# mowbot.net
KiCad netlist of a schematic drawn in EAGLE
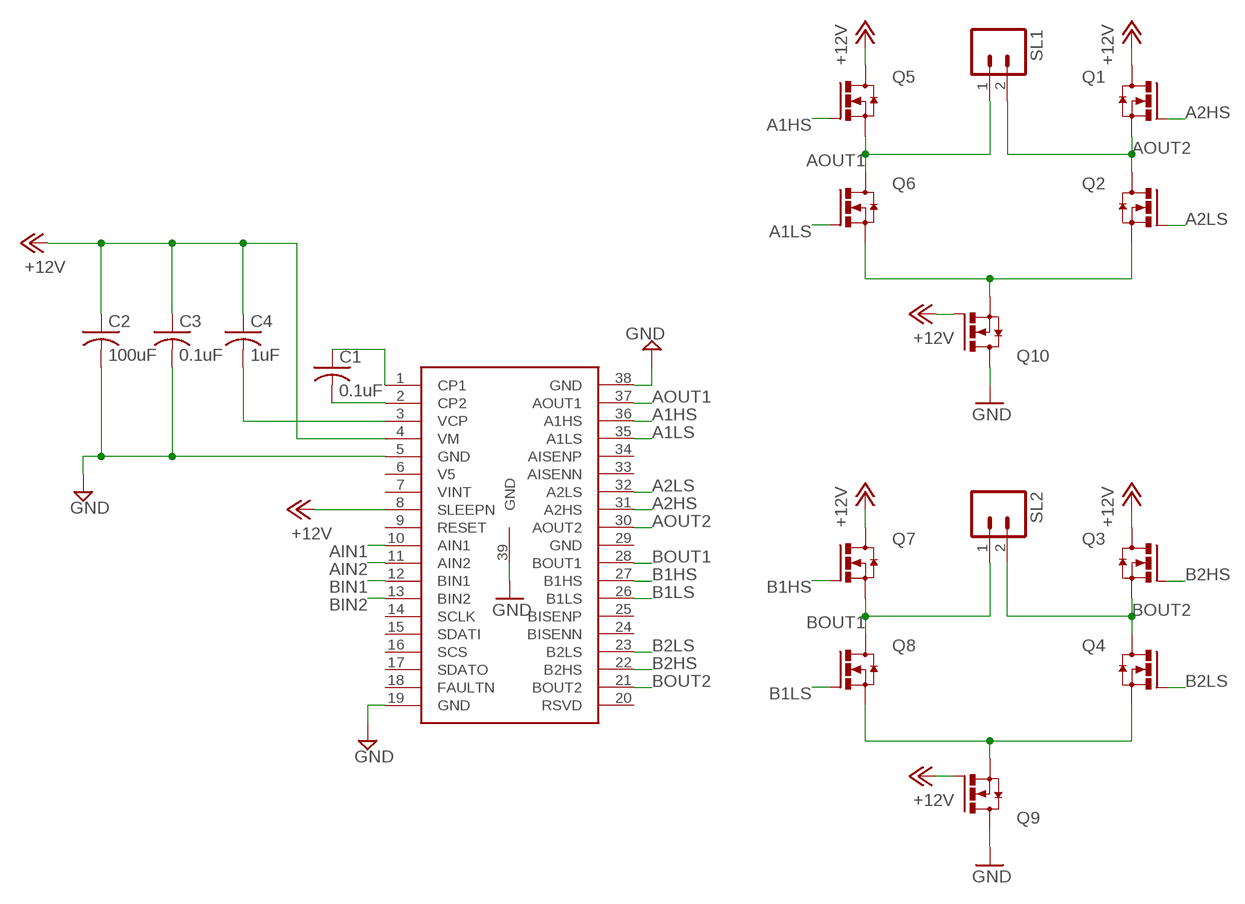
[diagram p0: schematic, sheet 1]
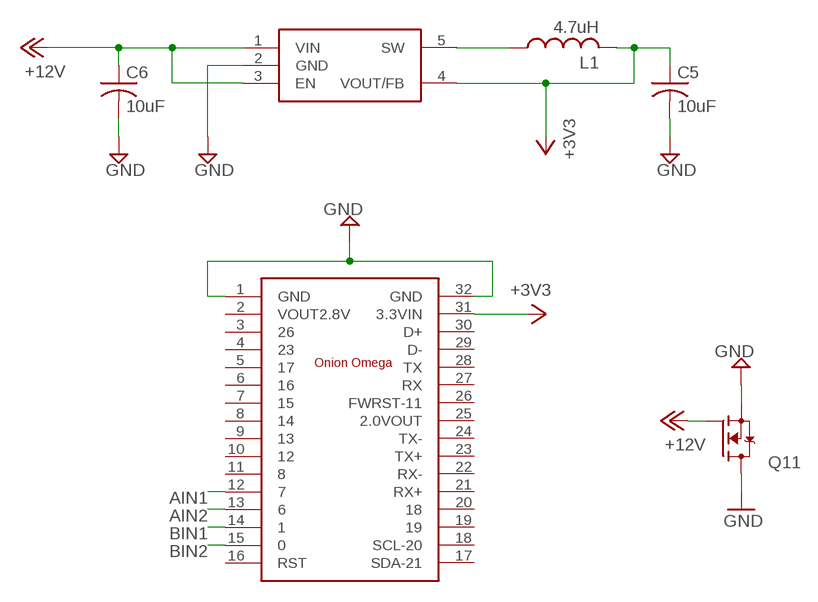
[diagram p1: schematic, sheet 2]

(export (version "E")
  (design (tool "Eeschema 10.0.6"))
  (components
    (comp (ref "C1")
      (value "0.1uF")
      (footprint "eagle-import:C0603")
      (libsource (lib "eagle-import") (part "C-USC0603"))
    )
    (comp (ref "C2")
      (value "100uF")
      (footprint "eagle-import:C0603")
      (libsource (lib "eagle-import") (part "C-USC0603"))
    )
    (comp (ref "C3")
      (value "0.1uF")
      (footprint "eagle-import:C0603")
      (libsource (lib "eagle-import") (part "C-USC0603"))
    )
    (comp (ref "C4")
      (value "1uF")
      (footprint "eagle-import:C0603")
      (libsource (lib "eagle-import") (part "C-USC0603"))
    )
    (comp (ref "Q1")
      (value "PSMN9R1-30YL-MOSFET_N")
      (footprint "eagle-import:SOT669")
      (libsource (lib "eagle-import") (part "PSMN9R1-30YL-MOSFET_N"))
    )
    (comp (ref "Q2")
      (value "PSMN9R1-30YL-MOSFET_N")
      (footprint "eagle-import:SOT669")
      (libsource (lib "eagle-import") (part "PSMN9R1-30YL-MOSFET_N"))
    )
    (comp (ref "Q3")
      (value "PSMN9R1-30YL-MOSFET_N")
      (footprint "eagle-import:SOT669")
      (libsource (lib "eagle-import") (part "PSMN9R1-30YL-MOSFET_N"))
    )
    (comp (ref "Q4")
      (value "PSMN9R1-30YL-MOSFET_N")
      (footprint "eagle-import:SOT669")
      (libsource (lib "eagle-import") (part "PSMN9R1-30YL-MOSFET_N"))
    )
    (comp (ref "Q5")
      (value "PSMN9R1-30YL-MOSFET_N")
      (footprint "eagle-import:SOT669")
      (libsource (lib "eagle-import") (part "PSMN9R1-30YL-MOSFET_N"))
    )
    (comp (ref "Q6")
      (value "PSMN9R1-30YL-MOSFET_N")
      (footprint "eagle-import:SOT669")
      (libsource (lib "eagle-import") (part "PSMN9R1-30YL-MOSFET_N"))
    )
    (comp (ref "Q7")
      (value "PSMN9R1-30YL-MOSFET_N")
      (footprint "eagle-import:SOT669")
      (libsource (lib "eagle-import") (part "PSMN9R1-30YL-MOSFET_N"))
    )
    (comp (ref "Q8")
      (value "PSMN9R1-30YL-MOSFET_N")
      (footprint "eagle-import:SOT669")
      (libsource (lib "eagle-import") (part "PSMN9R1-30YL-MOSFET_N"))
    )
    (comp (ref "Q9")
      (value "PSMN9R1-30YL-MOSFET_N")
      (footprint "eagle-import:SOT669")
      (libsource (lib "eagle-import") (part "PSMN9R1-30YL-MOSFET_N"))
    )
    (comp (ref "Q10")
      (value "PSMN9R1-30YL-MOSFET_N")
      (footprint "eagle-import:SOT669")
      (libsource (lib "eagle-import") (part "PSMN9R1-30YL-MOSFET_N"))
    )
    (comp (ref "SL1")
      (value "M02")
      (footprint "eagle-import:02P")
      (libsource (lib "eagle-import") (part "M02"))
    )
    (comp (ref "SL2")
      (value "M02")
      (footprint "eagle-import:02P")
      (libsource (lib "eagle-import") (part "M02"))
    )
    (comp (ref "U$1")
      (value "DRV8704-HBRIDGE_DRIVER")
      (footprint "eagle-import:DRV8704-HBRIDGE-DRIVER")
      (libsource (lib "eagle-import") (part "DRV8704-HBRIDGE_DRIVER"))
    )
    (comp (ref "C5")
      (value "10uF")
      (footprint "eagle-import:C0603")
      (libsource (lib "eagle-import") (part "C-USC0603"))
    )
    (comp (ref "C6")
      (value "10uF")
      (footprint "eagle-import:C0603")
      (libsource (lib "eagle-import") (part "C-USC0603"))
    )
    (comp (ref "L1")
      (value "4.7uH")
      (footprint "eagle-import:L1812")
      (libsource (lib "eagle-import") (part "L-USL1812"))
    )
    (comp (ref "Q11")
      (value "DMG2302UK-NMOSFET")
      (footprint "eagle-import:SOT23")
      (libsource (lib "eagle-import") (part "DMG2302UK-NMOSFET"))
    )
    (comp (ref "U$2")
      (value "ONION_OMEGA")
      (footprint "eagle-import:ONION_OMEGA")
      (libsource (lib "eagle-import") (part "ONION_OMEGA"))
    )
    (comp (ref "U$3")
      (value "PAM2305")
      (footprint "eagle-import:SOT23-5")
      (libsource (lib "eagle-import") (part "PAM2305"))
    )
  )
  (nets
    (net (code "1") (name "+3V3") (class "Default")
      (node (ref "C5") (pin "1") (pinfunction "1_1") (pintype "passive"))
      (node (ref "L1") (pin "2") (pinfunction "2_2") (pintype "passive"))
      (node (ref "U$2") (pin "31") (pinfunction "3.3VIN_31") (pintype "bidirectional"))
      (node (ref "U$3") (pin "4") (pinfunction "VOUT/FB_4") (pintype "bidirectional"))
    )
    (net (code "2") (name "+12V") (class "Default")
      (node (ref "C2") (pin "1") (pinfunction "1_1") (pintype "passive"))
      (node (ref "C3") (pin "1") (pinfunction "1_1") (pintype "passive"))
      (node (ref "C4") (pin "1") (pinfunction "1_1") (pintype "passive"))
      (node (ref "C6") (pin "1") (pinfunction "1_1") (pintype "passive"))
      (node (ref "Q1") (pin "MB") (pinfunction "D_MB") (pintype "passive"))
      (node (ref "Q10") (pin "4") (pinfunction "G_4") (pintype "passive"))
      (node (ref "Q11") (pin "1") (pinfunction "G_1") (pintype "passive"))
      (node (ref "Q3") (pin "MB") (pinfunction "D_MB") (pintype "passive"))
      (node (ref "Q5") (pin "MB") (pinfunction "D_MB") (pintype "passive"))
      (node (ref "Q7") (pin "MB") (pinfunction "D_MB") (pintype "passive"))
      (node (ref "Q9") (pin "4") (pinfunction "G_4") (pintype "passive"))
      (node (ref "U$1") (pin "4") (pinfunction "VM_4") (pintype "bidirectional"))
      (node (ref "U$1") (pin "8") (pinfunction "SLEEPN_8") (pintype "bidirectional"))
      (node (ref "U$3") (pin "1") (pinfunction "VIN_1") (pintype "bidirectional"))
      (node (ref "U$3") (pin "3") (pinfunction "EN_3") (pintype "bidirectional"))
    )
    (net (code "3") (name "A1HS") (class "Default")
      (node (ref "Q5") (pin "4") (pinfunction "G_4") (pintype "passive"))
      (node (ref "U$1") (pin "36") (pinfunction "A1HS_36") (pintype "bidirectional"))
    )
    (net (code "4") (name "A1LS") (class "Default")
      (node (ref "Q6") (pin "4") (pinfunction "G_4") (pintype "passive"))
      (node (ref "U$1") (pin "35") (pinfunction "A1LS_35") (pintype "bidirectional"))
    )
    (net (code "5") (name "A2HS") (class "Default")
      (node (ref "Q1") (pin "4") (pinfunction "G_4") (pintype "passive"))
      (node (ref "U$1") (pin "31") (pinfunction "A2HS_31") (pintype "bidirectional"))
    )
    (net (code "6") (name "A2LS") (class "Default")
      (node (ref "Q2") (pin "4") (pinfunction "G_4") (pintype "passive"))
      (node (ref "U$1") (pin "32") (pinfunction "A2LS_32") (pintype "bidirectional"))
    )
    (net (code "7") (name "AIN1") (class "Default")
      (node (ref "U$1") (pin "10") (pinfunction "AIN1_10") (pintype "bidirectional"))
      (node (ref "U$2") (pin "12") (pinfunction "7_12") (pintype "bidirectional"))
    )
    (net (code "8") (name "AIN2") (class "Default")
      (node (ref "U$1") (pin "11") (pinfunction "AIN2_11") (pintype "bidirectional"))
      (node (ref "U$2") (pin "13") (pinfunction "6_13") (pintype "bidirectional"))
    )
    (net (code "9") (name "AOUT1") (class "Default")
      (node (ref "Q5") (pin "1") (pinfunction "S_1") (pintype "passive"))
      (node (ref "Q5") (pin "2") (pinfunction "S_2") (pintype "passive"))
      (node (ref "Q5") (pin "3") (pinfunction "S_3") (pintype "passive"))
      (node (ref "Q6") (pin "MB") (pinfunction "D_MB") (pintype "passive"))
      (node (ref "SL1") (pin "1") (pinfunction "1_1") (pintype "passive"))
      (node (ref "U$1") (pin "37") (pinfunction "AOUT1_37") (pintype "bidirectional"))
    )
    (net (code "10") (name "AOUT2") (class "Default")
      (node (ref "Q1") (pin "1") (pinfunction "S_1") (pintype "passive"))
      (node (ref "Q1") (pin "2") (pinfunction "S_2") (pintype "passive"))
      (node (ref "Q1") (pin "3") (pinfunction "S_3") (pintype "passive"))
      (node (ref "Q2") (pin "MB") (pinfunction "D_MB") (pintype "passive"))
      (node (ref "SL1") (pin "2") (pinfunction "2_2") (pintype "passive"))
      (node (ref "U$1") (pin "30") (pinfunction "AOUT2_30") (pintype "bidirectional"))
    )
    (net (code "11") (name "B1HS") (class "Default")
      (node (ref "Q7") (pin "4") (pinfunction "G_4") (pintype "passive"))
      (node (ref "U$1") (pin "27") (pinfunction "B1HS_27") (pintype "bidirectional"))
    )
    (net (code "12") (name "B1LS") (class "Default")
      (node (ref "Q8") (pin "4") (pinfunction "G_4") (pintype "passive"))
      (node (ref "U$1") (pin "26") (pinfunction "B1LS_26") (pintype "bidirectional"))
    )
    (net (code "13") (name "B2HS") (class "Default")
      (node (ref "Q3") (pin "4") (pinfunction "G_4") (pintype "passive"))
      (node (ref "U$1") (pin "22") (pinfunction "B2HS_22") (pintype "bidirectional"))
    )
    (net (code "14") (name "B2LS") (class "Default")
      (node (ref "Q4") (pin "4") (pinfunction "G_4") (pintype "passive"))
      (node (ref "U$1") (pin "23") (pinfunction "B2LS_23") (pintype "bidirectional"))
    )
    (net (code "15") (name "BIN1") (class "Default")
      (node (ref "U$1") (pin "12") (pinfunction "BIN1_12") (pintype "bidirectional"))
      (node (ref "U$2") (pin "14") (pinfunction "1_14") (pintype "bidirectional"))
    )
    (net (code "16") (name "BIN2") (class "Default")
      (node (ref "U$1") (pin "13") (pinfunction "BIN2_13") (pintype "bidirectional"))
      (node (ref "U$2") (pin "15") (pinfunction "0_15") (pintype "bidirectional"))
    )
    (net (code "17") (name "BOUT1") (class "Default")
      (node (ref "Q7") (pin "1") (pinfunction "S_1") (pintype "passive"))
      (node (ref "Q7") (pin "2") (pinfunction "S_2") (pintype "passive"))
      (node (ref "Q7") (pin "3") (pinfunction "S_3") (pintype "passive"))
      (node (ref "Q8") (pin "MB") (pinfunction "D_MB") (pintype "passive"))
      (node (ref "SL2") (pin "1") (pinfunction "1_1") (pintype "passive"))
      (node (ref "U$1") (pin "28") (pinfunction "BOUT1_28") (pintype "bidirectional"))
    )
    (net (code "18") (name "BOUT2") (class "Default")
      (node (ref "Q3") (pin "1") (pinfunction "S_1") (pintype "passive"))
      (node (ref "Q3") (pin "2") (pinfunction "S_2") (pintype "passive"))
      (node (ref "Q3") (pin "3") (pinfunction "S_3") (pintype "passive"))
      (node (ref "Q4") (pin "MB") (pinfunction "D_MB") (pintype "passive"))
      (node (ref "SL2") (pin "2") (pinfunction "2_2") (pintype "passive"))
      (node (ref "U$1") (pin "21") (pinfunction "BOUT2_21") (pintype "bidirectional"))
    )
    (net (code "19") (name "GND") (class "Default")
      (node (ref "C2") (pin "2") (pinfunction "2_2") (pintype "passive"))
      (node (ref "C3") (pin "2") (pinfunction "2_2") (pintype "passive"))
      (node (ref "C5") (pin "2") (pinfunction "2_2") (pintype "passive"))
      (node (ref "C6") (pin "2") (pinfunction "2_2") (pintype "passive"))
      (node (ref "Q10") (pin "MB") (pinfunction "D_MB") (pintype "passive"))
      (node (ref "Q11") (pin "2") (pinfunction "S_2") (pintype "passive"))
      (node (ref "Q11") (pin "3") (pinfunction "D_3") (pintype "passive"))
      (node (ref "Q9") (pin "MB") (pinfunction "D_MB") (pintype "passive"))
      (node (ref "U$1") (pin "19") (pinfunction "GND_19") (pintype "bidirectional"))
      (node (ref "U$1") (pin "38") (pinfunction "GND_38") (pintype "bidirectional"))
      (node (ref "U$1") (pin "39") (pinfunction "GND_39") (pintype "bidirectional"))
      (node (ref "U$1") (pin "5") (pinfunction "GND_5") (pintype "bidirectional"))
      (node (ref "U$2") (pin "1") (pinfunction "GND_1") (pintype "bidirectional"))
      (node (ref "U$2") (pin "32") (pinfunction "GND_32") (pintype "bidirectional"))
      (node (ref "U$3") (pin "2") (pinfunction "GND_2") (pintype "bidirectional"))
    )
    (net (code "20") (name "Net-(Q4-S-Pad1)") (class "Default")
      (node (ref "Q4") (pin "1") (pinfunction "S_1") (pintype "passive"))
      (node (ref "Q4") (pin "2") (pinfunction "S_2") (pintype "passive"))
      (node (ref "Q4") (pin "3") (pinfunction "S_3") (pintype "passive"))
      (node (ref "Q8") (pin "1") (pinfunction "S_1") (pintype "passive"))
      (node (ref "Q8") (pin "2") (pinfunction "S_2") (pintype "passive"))
      (node (ref "Q8") (pin "3") (pinfunction "S_3") (pintype "passive"))
      (node (ref "Q9") (pin "1") (pinfunction "S_1") (pintype "passive"))
      (node (ref "Q9") (pin "2") (pinfunction "S_2") (pintype "passive"))
      (node (ref "Q9") (pin "3") (pinfunction "S_3") (pintype "passive"))
    )
    (net (code "21") (name "Net-(Q10-S-Pad1)") (class "Default")
      (node (ref "Q10") (pin "1") (pinfunction "S_1") (pintype "passive"))
      (node (ref "Q10") (pin "2") (pinfunction "S_2") (pintype "passive"))
      (node (ref "Q10") (pin "3") (pinfunction "S_3") (pintype "passive"))
      (node (ref "Q2") (pin "1") (pinfunction "S_1") (pintype "passive"))
      (node (ref "Q2") (pin "2") (pinfunction "S_2") (pintype "passive"))
      (node (ref "Q2") (pin "3") (pinfunction "S_3") (pintype "passive"))
      (node (ref "Q6") (pin "1") (pinfunction "S_1") (pintype "passive"))
      (node (ref "Q6") (pin "2") (pinfunction "S_2") (pintype "passive"))
      (node (ref "Q6") (pin "3") (pinfunction "S_3") (pintype "passive"))
    )
    (net (code "22") (name "Net-(U$1-CP1)") (class "Default")
      (node (ref "C1") (pin "1") (pinfunction "1_1") (pintype "passive"))
      (node (ref "U$1") (pin "1") (pinfunction "CP1_1") (pintype "bidirectional"))
    )
    (net (code "23") (name "Net-(U$1-CP2)") (class "Default")
      (node (ref "C1") (pin "2") (pinfunction "2_2") (pintype "passive"))
      (node (ref "U$1") (pin "2") (pinfunction "CP2_2") (pintype "bidirectional"))
    )
    (net (code "24") (name "Net-(U$1-VCP)") (class "Default")
      (node (ref "C4") (pin "2") (pinfunction "2_2") (pintype "passive"))
      (node (ref "U$1") (pin "3") (pinfunction "VCP_3") (pintype "bidirectional"))
    )
    (net (code "25") (name "Net-(U$3-SW)") (class "Default")
      (node (ref "L1") (pin "1") (pinfunction "1_1") (pintype "passive"))
      (node (ref "U$3") (pin "5") (pinfunction "SW_5") (pintype "bidirectional"))
    )
    (net (code "26") (name "unconnected-(U$1-AISENN-Pad33)") (class "Default")
      (node (ref "U$1") (pin "33") (pinfunction "AISENN_33") (pintype "bidirectional"))
    )
    (net (code "27") (name "unconnected-(U$1-AISENP-Pad34)") (class "Default")
      (node (ref "U$1") (pin "34") (pinfunction "AISENP_34") (pintype "bidirectional"))
    )
    (net (code "28") (name "unconnected-(U$1-BISENN-Pad24)") (class "Default")
      (node (ref "U$1") (pin "24") (pinfunction "BISENN_24") (pintype "bidirectional"))
    )
    (net (code "29") (name "unconnected-(U$1-BISENP-Pad25)") (class "Default")
      (node (ref "U$1") (pin "25") (pinfunction "BISENP_25") (pintype "bidirectional"))
    )
    (net (code "30") (name "unconnected-(U$1-FAULTN-Pad18)") (class "Default")
      (node (ref "U$1") (pin "18") (pinfunction "FAULTN_18") (pintype "bidirectional"))
    )
    (net (code "31") (name "unconnected-(U$1-GND-Pad29)") (class "Default")
      (node (ref "U$1") (pin "29") (pinfunction "GND_29") (pintype "bidirectional"))
    )
    (net (code "32") (name "unconnected-(U$1-RESET-Pad9)") (class "Default")
      (node (ref "U$1") (pin "9") (pinfunction "RESET_9") (pintype "bidirectional"))
    )
    (net (code "33") (name "unconnected-(U$1-RSVD-Pad20)") (class "Default")
      (node (ref "U$1") (pin "20") (pinfunction "RSVD_20") (pintype "bidirectional"))
    )
    (net (code "34") (name "unconnected-(U$1-SCLK-Pad14)") (class "Default")
      (node (ref "U$1") (pin "14") (pinfunction "SCLK_14") (pintype "bidirectional"))
    )
    (net (code "35") (name "unconnected-(U$1-SCS-Pad16)") (class "Default")
      (node (ref "U$1") (pin "16") (pinfunction "SCS_16") (pintype "bidirectional"))
    )
    (net (code "36") (name "unconnected-(U$1-SDATI-Pad15)") (class "Default")
      (node (ref "U$1") (pin "15") (pinfunction "SDATI_15") (pintype "bidirectional"))
    )
    (net (code "37") (name "unconnected-(U$1-SDATO-Pad17)") (class "Default")
      (node (ref "U$1") (pin "17") (pinfunction "SDATO_17") (pintype "bidirectional"))
    )
    (net (code "38") (name "unconnected-(U$1-V5-Pad6)") (class "Default")
      (node (ref "U$1") (pin "6") (pinfunction "V5_6") (pintype "bidirectional"))
    )
    (net (code "39") (name "unconnected-(U$1-VINT-Pad7)") (class "Default")
      (node (ref "U$1") (pin "7") (pinfunction "VINT_7") (pintype "bidirectional"))
    )
    (net (code "40") (name "unconnected-(U$2-2.0VOUT-Pad25)") (class "Default")
      (node (ref "U$2") (pin "25") (pinfunction "2.0VOUT_25") (pintype "bidirectional"))
    )
    (net (code "41") (name "unconnected-(U$2-8-Pad11)") (class "Default")
      (node (ref "U$2") (pin "11") (pinfunction "8_11") (pintype "bidirectional"))
    )
    (net (code "42") (name "unconnected-(U$2-12-Pad10)") (class "Default")
      (node (ref "U$2") (pin "10") (pinfunction "12_10") (pintype "bidirectional"))
    )
    (net (code "43") (name "unconnected-(U$2-13-Pad9)") (class "Default")
      (node (ref "U$2") (pin "9") (pinfunction "13_9") (pintype "bidirectional"))
    )
    (net (code "44") (name "unconnected-(U$2-14-Pad8)") (class "Default")
      (node (ref "U$2") (pin "8") (pinfunction "14_8") (pintype "bidirectional"))
    )
    (net (code "45") (name "unconnected-(U$2-15-Pad7)") (class "Default")
      (node (ref "U$2") (pin "7") (pinfunction "15_7") (pintype "bidirectional"))
    )
    (net (code "46") (name "unconnected-(U$2-16-Pad6)") (class "Default")
      (node (ref "U$2") (pin "6") (pinfunction "16_6") (pintype "bidirectional"))
    )
    (net (code "47") (name "unconnected-(U$2-17-Pad5)") (class "Default")
      (node (ref "U$2") (pin "5") (pinfunction "17_5") (pintype "bidirectional"))
    )
    (net (code "48") (name "unconnected-(U$2-18-Pad20)") (class "Default")
      (node (ref "U$2") (pin "20") (pinfunction "18_20") (pintype "bidirectional"))
    )
    (net (code "49") (name "unconnected-(U$2-23-Pad4)") (class "Default")
      (node (ref "U$2") (pin "4") (pinfunction "23_4") (pintype "bidirectional"))
    )
    (net (code "50") (name "unconnected-(U$2-26-Pad3)") (class "Default")
      (node (ref "U$2") (pin "3") (pinfunction "26_3") (pintype "bidirectional"))
    )
    (net (code "51") (name "unconnected-(U$2-D+-Pad30)") (class "Default")
      (node (ref "U$2") (pin "30") (pinfunction "D+_30") (pintype "bidirectional"))
    )
    (net (code "52") (name "unconnected-(U$2-D--Pad29)") (class "Default")
      (node (ref "U$2") (pin "29") (pinfunction "D-_29") (pintype "bidirectional"))
    )
    (net (code "53") (name "unconnected-(U$2-FWRST-11-Pad26)") (class "Default")
      (node (ref "U$2") (pin "26") (pinfunction "FWRST-11_26") (pintype "bidirectional"))
    )
    (net (code "54") (name "unconnected-(U$2-Pad19)") (class "Default")
      (node (ref "U$2") (pin "19") (pinfunction "19_19") (pintype "bidirectional"))
    )
    (net (code "55") (name "unconnected-(U$2-RST-Pad16)") (class "Default")
      (node (ref "U$2") (pin "16") (pinfunction "RST_16") (pintype "bidirectional"))
    )
    (net (code "56") (name "unconnected-(U$2-RX+-Pad21)") (class "Default")
      (node (ref "U$2") (pin "21") (pinfunction "RX+_21") (pintype "bidirectional"))
    )
    (net (code "57") (name "unconnected-(U$2-RX--Pad22)") (class "Default")
      (node (ref "U$2") (pin "22") (pinfunction "RX-_22") (pintype "bidirectional"))
    )
    (net (code "58") (name "unconnected-(U$2-RX-Pad27)") (class "Default")
      (node (ref "U$2") (pin "27") (pinfunction "RX_27") (pintype "bidirectional"))
    )
    (net (code "59") (name "unconnected-(U$2-SCL-20-Pad18)") (class "Default")
      (node (ref "U$2") (pin "18") (pinfunction "SCL-20_18") (pintype "bidirectional"))
    )
    (net (code "60") (name "unconnected-(U$2-SDA-21-Pad17)") (class "Default")
      (node (ref "U$2") (pin "17") (pinfunction "SDA-21_17") (pintype "bidirectional"))
    )
    (net (code "61") (name "unconnected-(U$2-TX+-Pad23)") (class "Default")
      (node (ref "U$2") (pin "23") (pinfunction "TX+_23") (pintype "bidirectional"))
    )
    (net (code "62") (name "unconnected-(U$2-TX--Pad24)") (class "Default")
      (node (ref "U$2") (pin "24") (pinfunction "TX-_24") (pintype "bidirectional"))
    )
    (net (code "63") (name "unconnected-(U$2-TX-Pad28)") (class "Default")
      (node (ref "U$2") (pin "28") (pinfunction "TX_28") (pintype "bidirectional"))
    )
    (net (code "64") (name "unconnected-(U$2-VOUT2.8V-Pad2)") (class "Default")
      (node (ref "U$2") (pin "2") (pinfunction "VOUT2.8V_2") (pintype "bidirectional"))
    )
  )
)
